# BlinkyBall.net
KiCad netlist of a schematic drawn in EAGLE
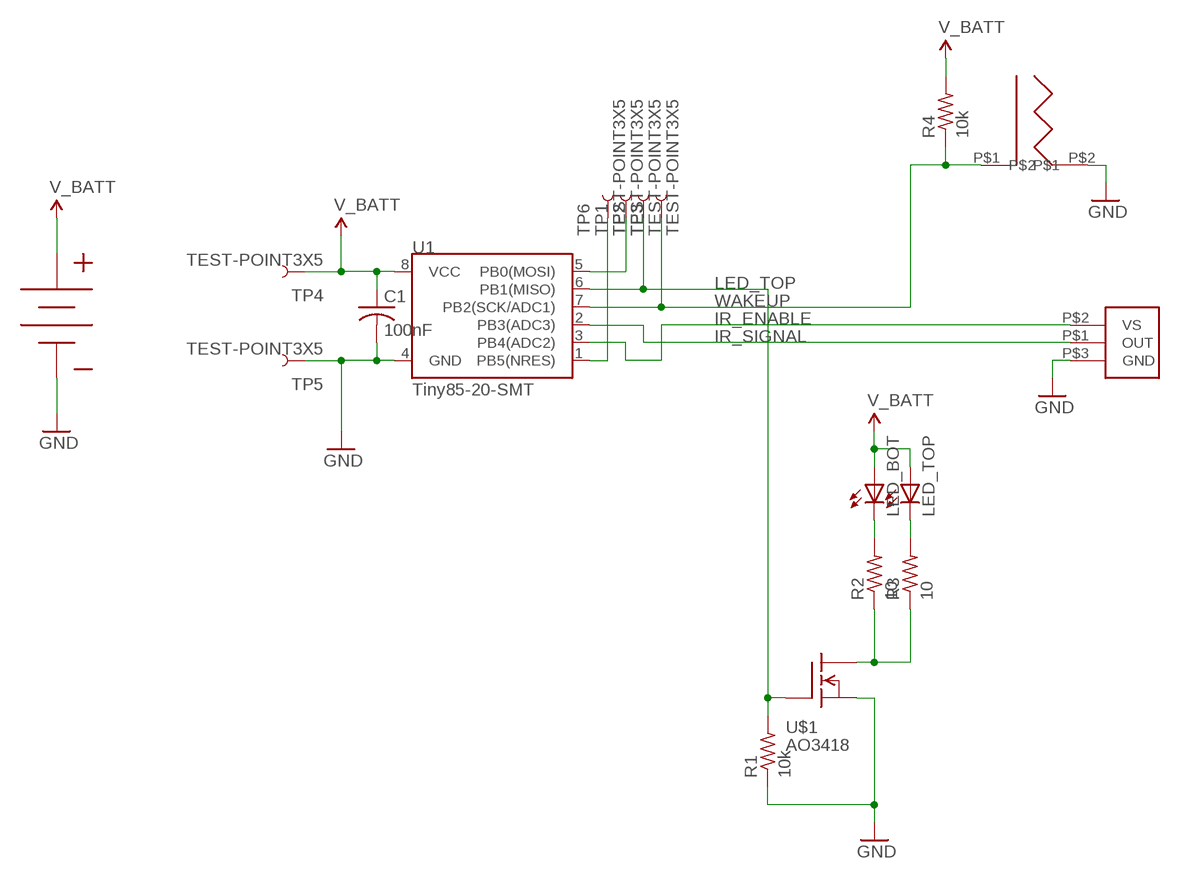
[diagram p0: schematic, sheet 1]

(export (version "E")
  (design (tool "Eeschema 10.0.6"))
  (components
    (comp (ref "C1")
      (value "100nF")
      (footprint "eagle-import:C0603")
      (libsource (lib "eagle-import") (part "C-USC0603"))
    )
    (comp (ref "LED_BOT")
      (value "LED5MM")
      (footprint "eagle-import:LED5MM")
      (libsource (lib "eagle-import") (part "LED5MM"))
    )
    (comp (ref "LED_TOP")
      (value "LED5MM")
      (footprint "eagle-import:LED5MM")
      (libsource (lib "eagle-import") (part "LED5MM"))
    )
    (comp (ref "R1")
      (value "10k")
      (footprint "eagle-import:R0603")
      (libsource (lib "eagle-import") (part "R-US_R0603"))
    )
    (comp (ref "R2")
      (value "10")
      (footprint "eagle-import:R0603")
      (libsource (lib "eagle-import") (part "R-US_R0603"))
    )
    (comp (ref "R3")
      (value "10")
      (footprint "eagle-import:R0603")
      (libsource (lib "eagle-import") (part "R-US_R0603"))
    )
    (comp (ref "R4")
      (value "10k")
      (footprint "eagle-import:R0603")
      (libsource (lib "eagle-import") (part "R-US_R0603"))
    )
    (comp (ref "TP1")
      (value "TEST-POINT3X5")
      (footprint "eagle-import:PAD.03X.05")
      (libsource (lib "eagle-import") (part "TEST-POINT3X5"))
    )
    (comp (ref "TP2")
      (value "TEST-POINT3X5")
      (footprint "eagle-import:PAD.03X.05")
      (libsource (lib "eagle-import") (part "TEST-POINT3X5"))
    )
    (comp (ref "TP3")
      (value "TEST-POINT3X5")
      (footprint "eagle-import:PAD.03X.05")
      (libsource (lib "eagle-import") (part "TEST-POINT3X5"))
    )
    (comp (ref "TP4")
      (value "TEST-POINT3X5")
      (footprint "eagle-import:PAD.03X.05")
      (libsource (lib "eagle-import") (part "TEST-POINT3X5"))
    )
    (comp (ref "TP5")
      (value "TEST-POINT3X5")
      (footprint "eagle-import:PAD.03X.05")
      (libsource (lib "eagle-import") (part "TEST-POINT3X5"))
    )
    (comp (ref "TP6")
      (value "TEST-POINT3X5")
      (footprint "eagle-import:PAD.03X.05")
      (libsource (lib "eagle-import") (part "TEST-POINT3X5"))
    )
    (comp (ref "U$1")
      (value "AO3418")
      (footprint "eagle-import:SOT23")
      (libsource (lib "eagle-import") (part "N_MOSFETSOT23"))
    )
    (comp (ref "U$2")
      (value "BATTERY_BUTTON_CELLAG3")
      (footprint "eagle-import:BATTERY_COVER_AG3")
      (libsource (lib "eagle-import") (part "BATTERY_BUTTON_CELLAG3"))
    )
    (comp (ref "U$3")
      (value "SW-18015P")
      (footprint "eagle-import:SW-18015P")
      (libsource (lib "eagle-import") (part "SW-18015P"))
    )
    (comp (ref "U$5")
      (value "TSOP321")
      (footprint "eagle-import:TSOP321")
      (libsource (lib "eagle-import") (part "TSOP321"))
    )
    (comp (ref "U1")
      (value "Tiny85-20-SMT")
      (footprint "eagle-import:SO08-EIAJ")
      (libsource (lib "eagle-import") (part "ATTINY45TINY85-20-SMT"))
    )
  )
  (nets
    (net (code "1") (name "/IR_ENABLE") (class "Default")
      (node (ref "U$5") (pin "P$2") (pinfunction "VS_P$2") (pintype "bidirectional"))
      (node (ref "U1") (pin "3") (pinfunction "PB4(ADC2)_3") (pintype "bidirectional"))
    )
    (net (code "2") (name "/IR_SIGNAL") (class "Default")
      (node (ref "U$5") (pin "P$1") (pinfunction "OUT_P$1") (pintype "bidirectional"))
      (node (ref "U1") (pin "2") (pinfunction "PB3(ADC3)_2") (pintype "bidirectional"))
    )
    (net (code "3") (name "/LED_TOP") (class "Default")
      (node (ref "R1") (pin "2") (pinfunction "2_2") (pintype "passive"))
      (node (ref "TP2") (pin "P$1") (pinfunction "1_P$1") (pintype "bidirectional"))
      (node (ref "U$1") (pin "1") (pinfunction "G_1") (pintype "bidirectional"))
      (node (ref "U1") (pin "6") (pinfunction "PB1(MISO)_6") (pintype "bidirectional"))
    )
    (net (code "4") (name "/WAKEUP") (class "Default")
      (node (ref "R4") (pin "1") (pinfunction "1_1") (pintype "passive"))
      (node (ref "TP3") (pin "P$1") (pinfunction "1_P$1") (pintype "bidirectional"))
      (node (ref "U$3") (pin "P$1") (pinfunction "P$1_P$1") (pintype "bidirectional"))
      (node (ref "U1") (pin "7") (pinfunction "PB2(SCK/ADC1)_7") (pintype "bidirectional"))
    )
    (net (code "5") (name "GND") (class "Default")
      (node (ref "C1") (pin "2") (pinfunction "2_2") (pintype "passive"))
      (node (ref "R1") (pin "1") (pinfunction "1_1") (pintype "passive"))
      (node (ref "TP5") (pin "P$1") (pinfunction "1_P$1") (pintype "bidirectional"))
      (node (ref "U$1") (pin "2") (pinfunction "S_2") (pintype "bidirectional"))
      (node (ref "U$2") (pin "-") (pinfunction "-_-") (pintype "power_in"))
      (node (ref "U$3") (pin "P$2") (pinfunction "P$2_P$2") (pintype "bidirectional"))
      (node (ref "U$5") (pin "P$3") (pinfunction "GND_P$3") (pintype "bidirectional"))
      (node (ref "U1") (pin "4") (pinfunction "GND_4") (pintype "bidirectional"))
    )
    (net (code "6") (name "Net-(LED_BOT-C)") (class "Default")
      (node (ref "LED_BOT") (pin "K") (pinfunction "C_K") (pintype "passive"))
      (node (ref "R2") (pin "2") (pinfunction "2_2") (pintype "passive"))
    )
    (net (code "7") (name "Net-(LED_TOP-C)") (class "Default")
      (node (ref "LED_TOP") (pin "K") (pinfunction "C_K") (pintype "passive"))
      (node (ref "R3") (pin "2") (pinfunction "2_2") (pintype "passive"))
    )
    (net (code "8") (name "Net-(TP1-1)") (class "Default")
      (node (ref "TP1") (pin "P$1") (pinfunction "1_P$1") (pintype "bidirectional"))
      (node (ref "U1") (pin "5") (pinfunction "PB0(MOSI)_5") (pintype "bidirectional"))
    )
    (net (code "9") (name "Net-(TP6-1)") (class "Default")
      (node (ref "TP6") (pin "P$1") (pinfunction "1_P$1") (pintype "bidirectional"))
      (node (ref "U1") (pin "1") (pinfunction "PB5(NRES)_1") (pintype "bidirectional"))
    )
    (net (code "10") (name "Net-(U$1-D)") (class "Default")
      (node (ref "R2") (pin "1") (pinfunction "1_1") (pintype "passive"))
      (node (ref "R3") (pin "1") (pinfunction "1_1") (pintype "passive"))
      (node (ref "U$1") (pin "3") (pinfunction "D_3") (pintype "bidirectional"))
    )
    (net (code "11") (name "V_BATT") (class "Default")
      (node (ref "C1") (pin "1") (pinfunction "1_1") (pintype "passive"))
      (node (ref "LED_BOT") (pin "A") (pinfunction "A_A") (pintype "passive"))
      (node (ref "LED_TOP") (pin "A") (pinfunction "A_A") (pintype "passive"))
      (node (ref "R4") (pin "2") (pinfunction "2_2") (pintype "passive"))
      (node (ref "TP4") (pin "P$1") (pinfunction "1_P$1") (pintype "bidirectional"))
      (node (ref "U$2") (pin "+1") (pinfunction "+_+1") (pintype "power_in"))
      (node (ref "U$2") (pin "+2") (pinfunction "+_+2") (pintype "power_in"))
      (node (ref "U$2") (pin "+3") (pinfunction "+_+3") (pintype "power_in"))
      (node (ref "U$2") (pin "+4") (pinfunction "+_+4") (pintype "power_in"))
      (node (ref "U1") (pin "8") (pinfunction "VCC_8") (pintype "bidirectional"))
    )
  )
)
